# Ethernet2_MDIO.net
KiCad netlist of a schematic drawn in Altium Designer
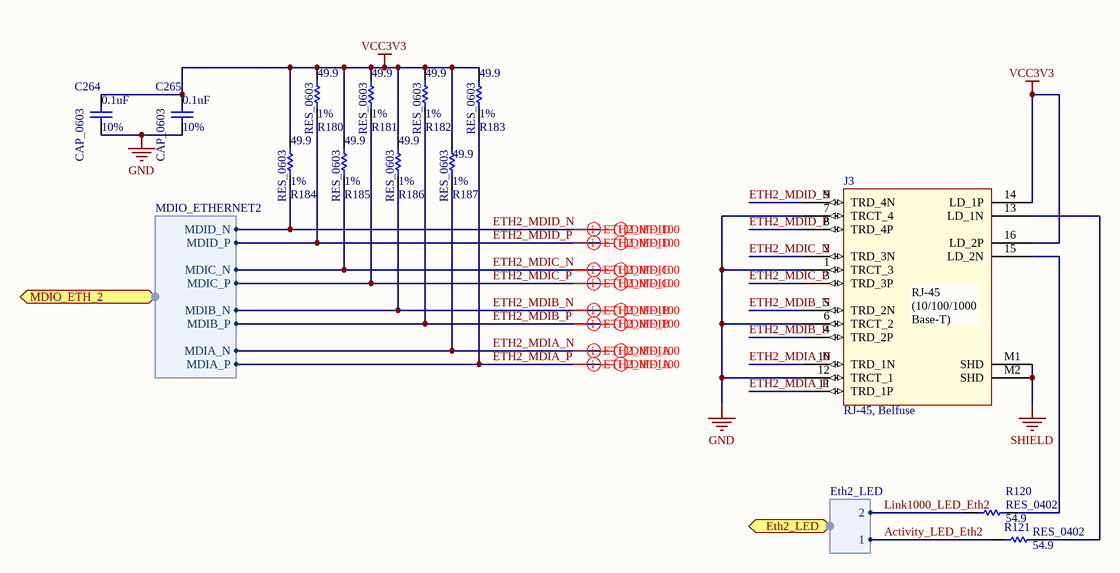
[diagram p0: Ethernet2_MDIO.SchDoc]

(export (version "E")
  (design (tool "Eeschema 10.0.6"))
  (components
    (comp (ref "C264")
      (value "CAP_0603")
      (footprint "CAPC0603(1608)100_N:CAPC0603(1608)100_N")
      (description "CAP CER 0.1UF 50V 10% X7R 0603")
      (fields
        (field (name "ALTIUM_VALUE") "0.1uF")
        (field (name "TOLERANCE") "10%")
        (field (name "PART NUMBER") "C0603C104K5RACTU")
        (field (name "MANUFACTURER") "Kemet")
      )
      (libsource (lib "COMRAD_Database") (part "CAP_0603"))
    )
    (comp (ref "C265")
      (value "CAP_0603")
      (footprint "CAPC0603(1608)100_N:CAPC0603(1608)100_N")
      (description "CAP CER 0.1UF 50V 10% X7R 0603")
      (fields
        (field (name "ALTIUM_VALUE") "0.1uF")
        (field (name "TOLERANCE") "10%")
        (field (name "PART NUMBER") "C0603C104K5RACTU")
        (field (name "MANUFACTURER") "Kemet")
      )
      (libsource (lib "COMRAD_Database") (part "CAP_0603"))
    )
    (comp (ref "J3")
      (value "RJ-45, Belfuse")
      (footprint "RJ-45_BelFuse_L834-1G1T-S7_pcb")
      (description "RJ-45, Belfuse, Gigabit Magnetic Jack")
      (fields (field (name "PART NUMBER") "L834-1G1T-S7") (field (name "MANUFACTURER") "Belfuse"))
      (libsource (lib "COMRAD_Database") (part "RJ-45_BelFuse_L8341GITS7"))
    )
    (comp (ref "R120")
      (value "RES_0402")
      (footprint "RESC0402(1005)_N")
      (description "RES 54.9 OHM 1/10W 1% 0402 SMD")
      (fields
        (field (name "ALTIUM_VALUE") "54.9")
        (field (name "PART NUMBER") "ERJ-2RKF54R9X")
        (field (name "MANUFACTURER") "Panasonic Electronic Components")
      )
      (libsource (lib "COMRAD_Database") (part "RES_0402"))
    )
    (comp (ref "R121")
      (value "RES_0402")
      (footprint "RESC0402(1005)_N")
      (description "RES 54.9 OHM 1/10W 1% 0402 SMD")
      (fields
        (field (name "ALTIUM_VALUE") "54.9")
        (field (name "PART NUMBER") "ERJ-2RKF54R9X")
        (field (name "MANUFACTURER") "Panasonic Electronic Components")
      )
      (libsource (lib "COMRAD_Database") (part "RES_0402"))
    )
    (comp (ref "R180")
      (value "RES_0603")
      (footprint "RESC0603(1608)_N")
      (description "RES 49.9 OHM 1/10W 1% 0603 SMD")
      (fields
        (field (name "ALTIUM_VALUE") "49.9")
        (field (name "TOLERANCE") "1%")
        (field (name "PART NUMBER") "ERJ-3EKF49R9V")
        (field (name "MANUFACTURER") "Panasonic Electronics Components")
      )
      (libsource (lib "COMRAD_Database") (part "RES_0603"))
    )
    (comp (ref "R181")
      (value "RES_0603")
      (footprint "RESC0603(1608)_N")
      (description "RES 49.9 OHM 1/10W 1% 0603 SMD")
      (fields
        (field (name "ALTIUM_VALUE") "49.9")
        (field (name "TOLERANCE") "1%")
        (field (name "PART NUMBER") "ERJ-3EKF49R9V")
        (field (name "MANUFACTURER") "Panasonic Electronics Components")
      )
      (libsource (lib "COMRAD_Database") (part "RES_0603"))
    )
    (comp (ref "R182")
      (value "RES_0603")
      (footprint "RESC0603(1608)_N")
      (description "RES 49.9 OHM 1/10W 1% 0603 SMD")
      (fields
        (field (name "ALTIUM_VALUE") "49.9")
        (field (name "TOLERANCE") "1%")
        (field (name "PART NUMBER") "ERJ-3EKF49R9V")
        (field (name "MANUFACTURER") "Panasonic Electronics Components")
      )
      (libsource (lib "COMRAD_Database") (part "RES_0603"))
    )
    (comp (ref "R183")
      (value "RES_0603")
      (footprint "RESC0603(1608)_N")
      (description "RES 49.9 OHM 1/10W 1% 0603 SMD")
      (fields
        (field (name "ALTIUM_VALUE") "49.9")
        (field (name "TOLERANCE") "1%")
        (field (name "PART NUMBER") "ERJ-3EKF49R9V")
        (field (name "MANUFACTURER") "Panasonic Electronics Components")
      )
      (libsource (lib "COMRAD_Database") (part "RES_0603"))
    )
    (comp (ref "R184")
      (value "RES_0603")
      (footprint "RESC0603(1608)_N")
      (description "RES 49.9 OHM 1/10W 1% 0603 SMD")
      (fields
        (field (name "ALTIUM_VALUE") "49.9")
        (field (name "TOLERANCE") "1%")
        (field (name "PART NUMBER") "ERJ-3EKF49R9V")
        (field (name "MANUFACTURER") "Panasonic Electronics Components")
      )
      (libsource (lib "COMRAD_Database") (part "RES_0603"))
    )
    (comp (ref "R185")
      (value "RES_0603")
      (footprint "RESC0603(1608)_N")
      (description "RES 49.9 OHM 1/10W 1% 0603 SMD")
      (fields
        (field (name "ALTIUM_VALUE") "49.9")
        (field (name "TOLERANCE") "1%")
        (field (name "PART NUMBER") "ERJ-3EKF49R9V")
        (field (name "MANUFACTURER") "Panasonic Electronics Components")
      )
      (libsource (lib "COMRAD_Database") (part "RES_0603"))
    )
    (comp (ref "R186")
      (value "RES_0603")
      (footprint "RESC0603(1608)_N")
      (description "RES 49.9 OHM 1/10W 1% 0603 SMD")
      (fields
        (field (name "ALTIUM_VALUE") "49.9")
        (field (name "TOLERANCE") "1%")
        (field (name "PART NUMBER") "ERJ-3EKF49R9V")
        (field (name "MANUFACTURER") "Panasonic Electronics Components")
      )
      (libsource (lib "COMRAD_Database") (part "RES_0603"))
    )
    (comp (ref "R187")
      (value "RES_0603")
      (footprint "RESC0603(1608)_N")
      (description "RES 49.9 OHM 1/10W 1% 0603 SMD")
      (fields
        (field (name "ALTIUM_VALUE") "49.9")
        (field (name "TOLERANCE") "1%")
        (field (name "PART NUMBER") "ERJ-3EKF49R9V")
        (field (name "MANUFACTURER") "Panasonic Electronics Components")
      )
      (libsource (lib "COMRAD_Database") (part "RES_0603"))
    )
  )
  (nets
    (net (code "3") (name "/Activity_LED_Eth2") (class "Default")
      (node (ref "R121") (pin "2") (pinfunction "2_2") (pintype "passive"))
    )
    (net (code "4") (name "/ETH2_MDIA_N") (class "Default")
      (node (ref "J3") (pin "10") (pinfunction "TRD_1N_10") (pintype "bidirectional"))
      (node (ref "R187") (pin "1") (pinfunction "1_1") (pintype "passive"))
    )
    (net (code "5") (name "/ETH2_MDIA_P") (class "Default")
      (node (ref "J3") (pin "11") (pinfunction "TRD_1P_11") (pintype "bidirectional"))
      (node (ref "R183") (pin "1") (pinfunction "1_1") (pintype "passive"))
    )
    (net (code "6") (name "/ETH2_MDIB_N") (class "Default")
      (node (ref "J3") (pin "5") (pinfunction "TRD_2N_5") (pintype "bidirectional"))
      (node (ref "R186") (pin "1") (pinfunction "1_1") (pintype "passive"))
    )
    (net (code "7") (name "/ETH2_MDIB_P") (class "Default")
      (node (ref "J3") (pin "4") (pinfunction "TRD_2P_4") (pintype "bidirectional"))
      (node (ref "R182") (pin "1") (pinfunction "1_1") (pintype "passive"))
    )
    (net (code "8") (name "/ETH2_MDIC_N") (class "Default")
      (node (ref "J3") (pin "2") (pinfunction "TRD_3N_2") (pintype "bidirectional"))
      (node (ref "R185") (pin "1") (pinfunction "1_1") (pintype "passive"))
    )
    (net (code "9") (name "/ETH2_MDIC_P") (class "Default")
      (node (ref "J3") (pin "3") (pinfunction "TRD_3P_3") (pintype "bidirectional"))
      (node (ref "R181") (pin "1") (pinfunction "1_1") (pintype "passive"))
    )
    (net (code "10") (name "/ETH2_MDID_N") (class "Default")
      (node (ref "J3") (pin "9") (pinfunction "TRD_4N_9") (pintype "bidirectional"))
      (node (ref "R184") (pin "1") (pinfunction "1_1") (pintype "passive"))
    )
    (net (code "11") (name "/ETH2_MDID_P") (class "Default")
      (node (ref "J3") (pin "8") (pinfunction "TRD_4P_8") (pintype "bidirectional"))
      (node (ref "R180") (pin "1") (pinfunction "1_1") (pintype "passive"))
    )
    (net (code "12") (name "/Link1000_LED_Eth2") (class "Default")
      (node (ref "R120") (pin "2") (pinfunction "2_2") (pintype "passive"))
    )
    (net (code "15") (name "GND") (class "Default")
      (node (ref "C264") (pin "1") (pinfunction "1_1") (pintype "passive"))
      (node (ref "C265") (pin "1") (pinfunction "1_1") (pintype "passive"))
      (node (ref "J3") (pin "1") (pinfunction "TRCT_3_1") (pintype "bidirectional"))
      (node (ref "J3") (pin "12") (pinfunction "TRCT_1_12") (pintype "bidirectional"))
      (node (ref "J3") (pin "6") (pinfunction "TRCT_2_6") (pintype "bidirectional"))
      (node (ref "J3") (pin "7") (pinfunction "TRCT_4_7") (pintype "bidirectional"))
    )
    (net (code "16") (name "Net-(J3-LD_1N)") (class "Default")
      (node (ref "J3") (pin "13") (pinfunction "LD_1N_13") (pintype "passive"))
      (node (ref "R121") (pin "1") (pinfunction "1_1") (pintype "passive"))
    )
    (net (code "17") (name "Net-(J3-LD_2N)") (class "Default")
      (node (ref "J3") (pin "15") (pinfunction "LD_2N_15") (pintype "passive"))
      (node (ref "R120") (pin "1") (pinfunction "1_1") (pintype "passive"))
    )
    (net (code "18") (name "SHIELD") (class "Default")
      (node (ref "J3") (pin "M1") (pinfunction "SHD_M1") (pintype "power_in"))
      (node (ref "J3") (pin "M2") (pinfunction "SHD_M2") (pintype "power_in"))
    )
    (net (code "19") (name "VCC3V3") (class "Default")
      (node (ref "C264") (pin "2") (pinfunction "2_2") (pintype "passive"))
      (node (ref "C265") (pin "2") (pinfunction "2_2") (pintype "passive"))
      (node (ref "J3") (pin "14") (pinfunction "LD_1P_14") (pintype "passive"))
      (node (ref "J3") (pin "16") (pinfunction "LD_2P_16") (pintype "passive"))
      (node (ref "R180") (pin "2") (pinfunction "2_2") (pintype "passive"))
      (node (ref "R181") (pin "2") (pinfunction "2_2") (pintype "passive"))
      (node (ref "R182") (pin "2") (pinfunction "2_2") (pintype "passive"))
      (node (ref "R183") (pin "2") (pinfunction "2_2") (pintype "passive"))
      (node (ref "R184") (pin "2") (pinfunction "2_2") (pintype "passive"))
      (node (ref "R185") (pin "2") (pinfunction "2_2") (pintype "passive"))
      (node (ref "R186") (pin "2") (pinfunction "2_2") (pintype "passive"))
      (node (ref "R187") (pin "2") (pinfunction "2_2") (pintype "passive"))
    )
  )
)
